# Power.net
KiCad netlist of a schematic drawn in Altium Designer
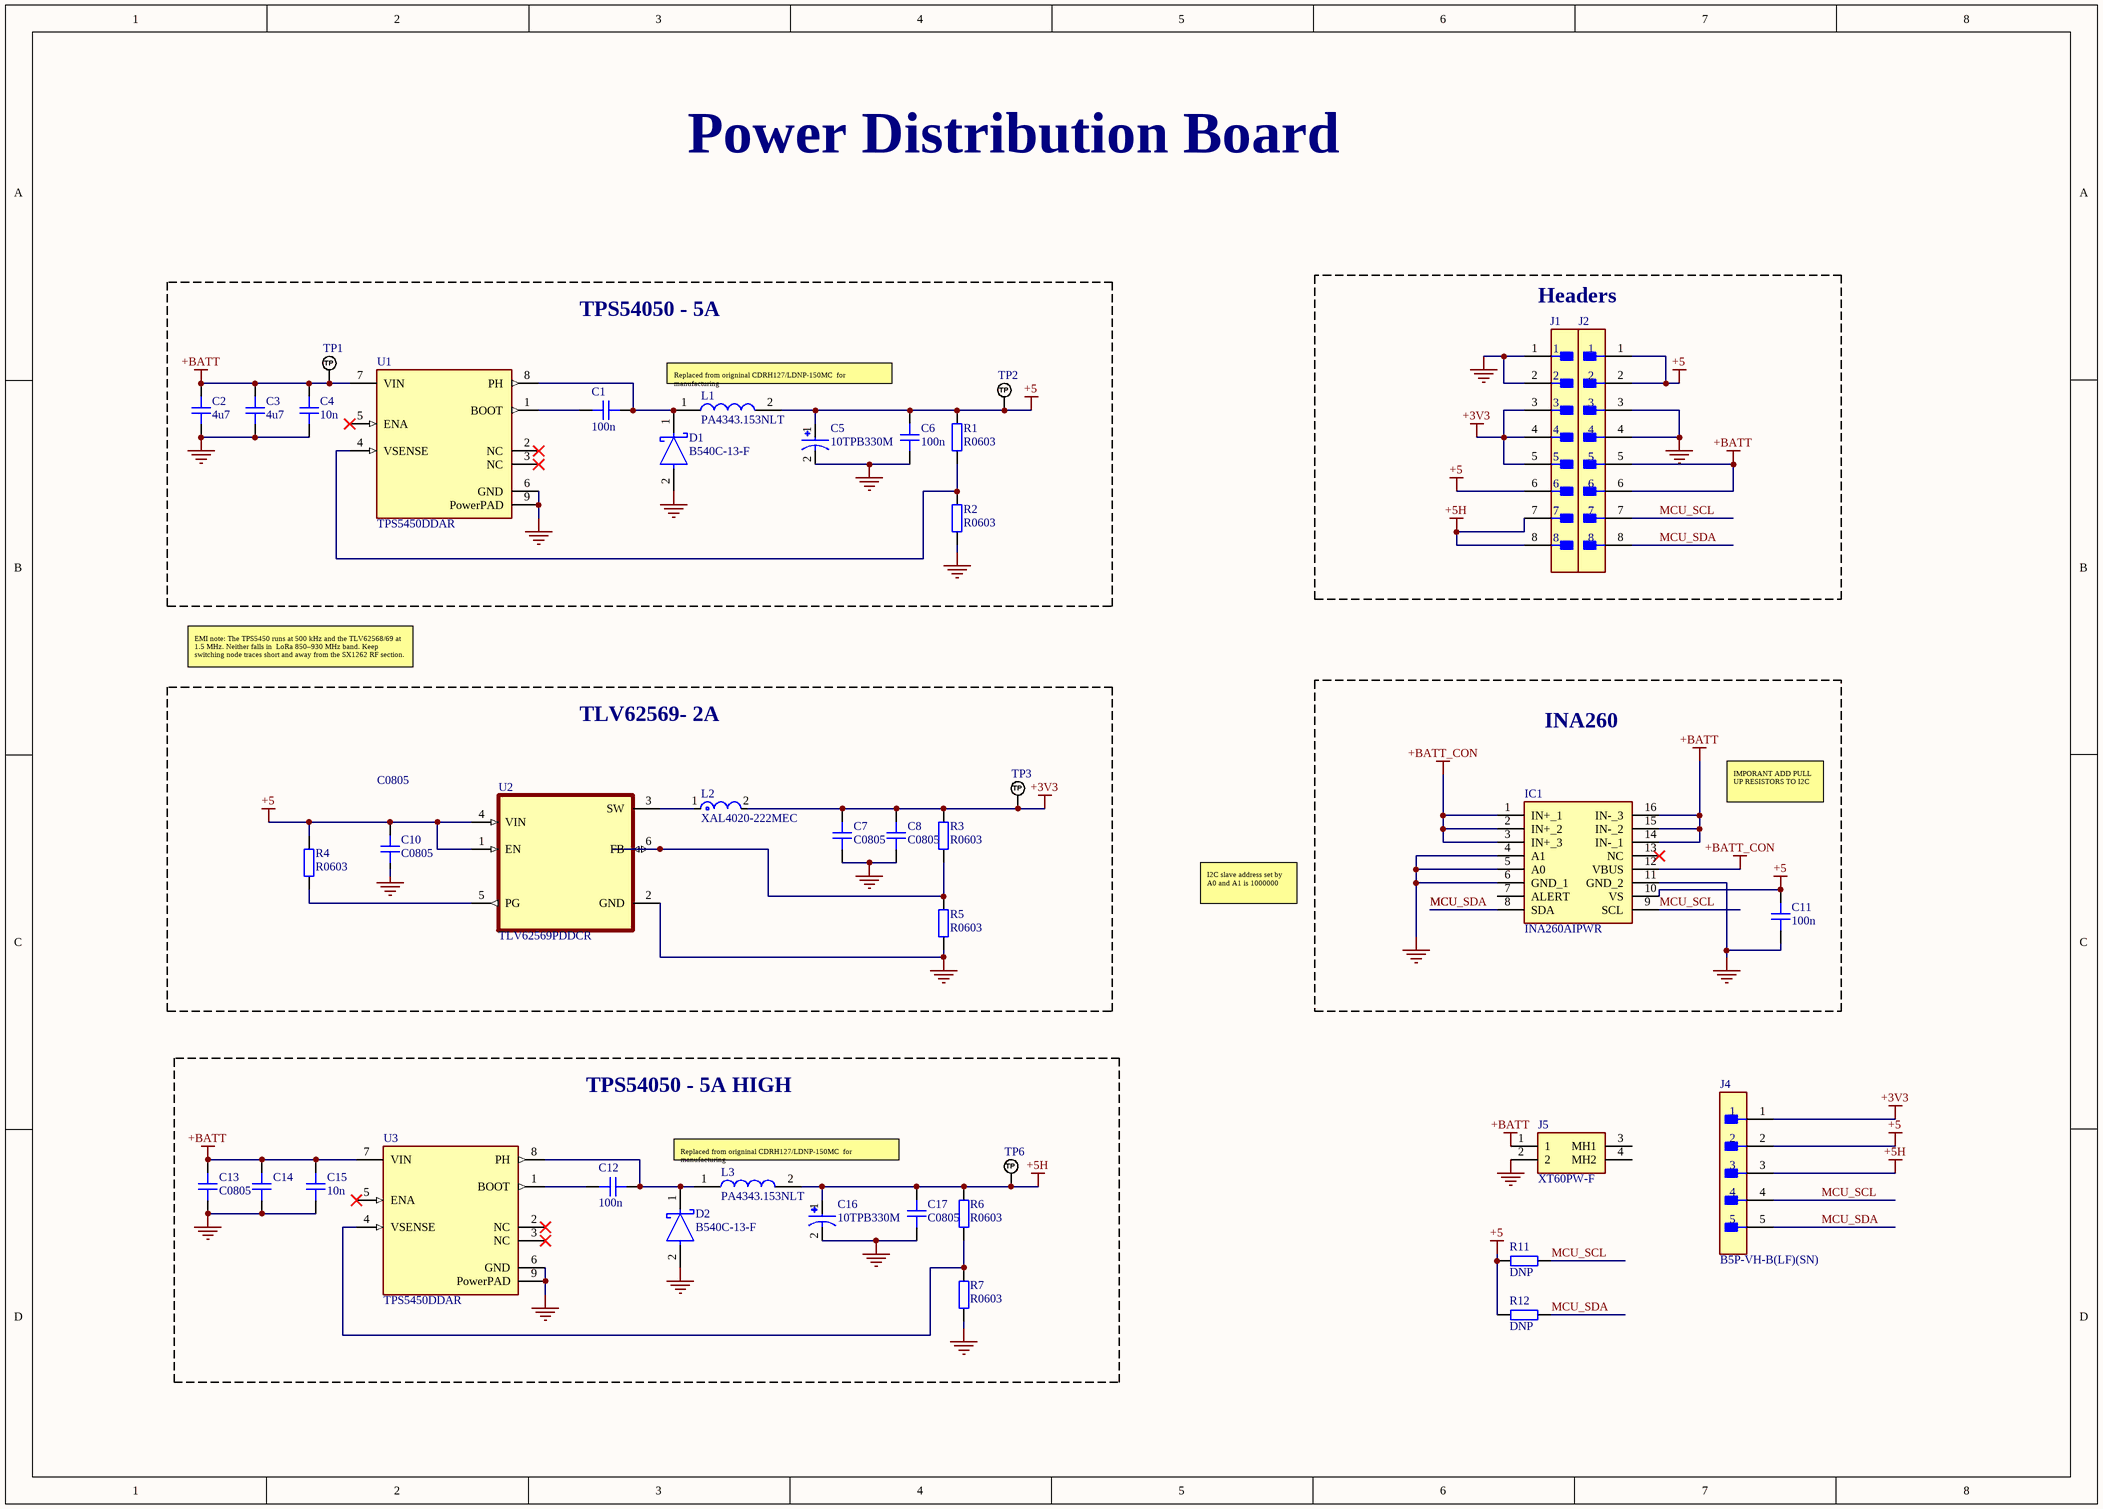
[diagram p0: Power.SchDoc]

(export (version "E")
  (design (tool "Eeschema 10.0.6"))
  (components
    (comp (ref "C1")
      (value "100n")
      (footprint "CAP_0603")
      (description "Capacitor SMD 0603")
      (libsource (lib "Powersch") (part "CAP_0603"))
    )
    (comp (ref "C2")
      (value "4u7")
      (footprint "CAP_0805")
      (description "Capacitor SMD 0805")
      (libsource (lib "Powersch") (part "CAP_0805"))
    )
    (comp (ref "C3")
      (value "4u7")
      (footprint "CAP_0805")
      (description "Capacitor SMD 0805")
      (libsource (lib "Powersch") (part "CAP_0805"))
    )
    (comp (ref "C4")
      (value "10n")
      (footprint "CAP_0603")
      (description "Capacitor SMD 0603")
      (libsource (lib "Powersch") (part "CAP_0603"))
    )
    (comp (ref "C5")
      (value "10TPB330M")
      (footprint "Powerpcblib:CAP_10TPB330M")
      (libsource (lib "Powersch") (part "10TPB330M"))
    )
    (comp (ref "C6")
      (value "100n")
      (footprint "CAP_0805")
      (description "Capacitor SMD 0805")
      (libsource (lib "Powersch") (part "CAP_0805"))
    )
    (comp (ref "C7")
      (value "C0805")
      (footprint "CAP_0805")
      (description "Capacitor SMD 0805")
      (libsource (lib "Powersch") (part "CAP_0805"))
    )
    (comp (ref "C8")
      (value "C0805")
      (footprint "CAP_0805")
      (description "Capacitor SMD 0805")
      (libsource (lib "Powersch") (part "CAP_0805"))
    )
    (comp (ref "C10")
      (value "C0805")
      (footprint "CAP_0805")
      (description "Capacitor SMD 0805")
      (libsource (lib "Powersch") (part "CAP_0805"))
    )
    (comp (ref "C11")
      (value "100n")
      (footprint "CAP_0603")
      (description "Capacitor SMD 0603")
      (libsource (lib "Powersch") (part "CAP_0603"))
    )
    (comp (ref "C12")
      (value "100n")
      (footprint "CAP_0603")
      (description "Capacitor SMD 0603")
      (libsource (lib "Powersch") (part "CAP_0603"))
    )
    (comp (ref "C13")
      (value "C0805")
      (footprint "CAP_0805")
      (description "Capacitor SMD 0805")
      (libsource (lib "Powersch") (part "CAP_0805"))
    )
    (comp (ref "C14")
      (value "C0805")
      (footprint "CAP_0805")
      (description "Capacitor SMD 0805")
      (libsource (lib "Powersch") (part "CAP_0805"))
    )
    (comp (ref "C15")
      (value "10n")
      (footprint "CAP_0603")
      (description "Capacitor SMD 0603")
      (libsource (lib "Powersch") (part "CAP_0603"))
    )
    (comp (ref "C16")
      (value "10TPB330M")
      (footprint "Powerpcblib:CAP_10TPB330M")
      (libsource (lib "Powersch") (part "10TPB330M"))
    )
    (comp (ref "C17")
      (value "C0805")
      (footprint "CAP_0805")
      (description "Capacitor SMD 0805")
      (libsource (lib "Powersch") (part "CAP_0805"))
    )
    (comp (ref "D1")
      (value "B540C-13-F")
      (footprint "FP-SMC-MFG")
      (description "DIODE SCHOTTKY 40V 5A SMC")
      (fields
        (field (name "OCTOPART") "https://octopart.com/b540c-13-f-diodes+inc.-325873")
        (field (name "MANUFACTURER") "Diodes Inc.")
      )
      (libsource (lib "Altium Content Vault") (part "1d6ec82d83fb6aee721767c19dac4b9"))
    )
    (comp (ref "D2")
      (value "B540C-13-F")
      (footprint "FP-SMC-MFG")
      (description "DIODE SCHOTTKY 40V 5A SMC")
      (fields
        (field (name "OCTOPART") "https://octopart.com/b540c-13-f-diodes+inc.-325873")
        (field (name "MANUFACTURER") "Diodes Inc.")
      )
      (libsource (lib "Altium Content Vault") (part "1d6ec82d83fb6aee721767c19dac4b9"))
    )
    (comp (ref "IC1")
      (value "INA260AIPWR")
      (footprint "Powerpcblib:SOP65P640X120-16N")
      (description "Integrated Circuit")
      (fields (field (name "MOUSER PART NUMBER") "595-INA260AIPWR"))
      (libsource (lib "Powersch") (part "INA260AIPWR"))
    )
    (comp (ref "J1")
      (value "TSW-108-08-G-S")
      (footprint "FP-TSW-108-08-G-S-MFG")
      (description "CONN HEADER VERT 8POS 2.54MM")
      (fields
        (field (name "MANUFACTURER") "Samtec")
        (field (name "OCTOPART") "https://octopart.com/tsw-108-08-g-s-samtec-272653")
      )
      (libsource (lib "") (part "99ec2b232beb5d2356d4d77f6a047f0_1"))
    )
    (comp (ref "J2")
      (value "TSW-108-08-G-S")
      (footprint "FP-TSW-108-08-G-S-MFG")
      (description "CONN HEADER VERT 8POS 2.54MM")
      (fields
        (field (name "MANUFACTURER") "Samtec")
        (field (name "OCTOPART") "https://octopart.com/tsw-108-08-g-s-samtec-272653")
      )
      (libsource (lib "Altium Content Vault") (part "99ec2b232beb5d2356d4d77f6a047f0"))
    )
    (comp (ref "J4")
      (value "B5P-VH-B(LF)(SN)")
      (footprint "FP-B5P-VH-B_LF_SN-MFG")
      (description "CONN HEADER VERT 5POS 3.96MM")
      (libsource (lib "Altium Content Vault") (part "bf93c07fd2649a848d0ec8585582aab"))
    )
    (comp (ref "J5")
      (value "XT60PW-F")
      (footprint "SamacSys:XT60PWF")
      (description "Connector")
      (libsource (lib "*") (part "XT60PW-F"))
    )
    (comp (ref "L1")
      (value "PA4343.153NLT")
      (footprint "SamacSys:INDPM140128X650N")
      (description "Inductor")
      (fields (field (name "MOUSER PART NUMBER") "673-PA4343.153NLT"))
      (libsource (lib "Powersch") (part "PA4343.153NLT"))
    )
    (comp (ref "L2")
      (value "XAL4020-222MEC")
      (footprint "FP-XAL4020-MFG")
      (description "Fixed Inductors 2.2uH Shld 20% 5.5A 38.7mOhms AECQ2")
      (fields (field (name "TOLERANCE") "20%"))
      (libsource (lib "Altium Content Vault") (part "4cc4b267dca4c8e51f7102f422741d8"))
    )
    (comp (ref "L3")
      (value "PA4343.153NLT")
      (footprint "SamacSys:INDPM140128X650N")
      (description "Inductor")
      (fields (field (name "MOUSER PART NUMBER") "673-PA4343.153NLT"))
      (libsource (lib "Powersch") (part "PA4343.153NLT"))
    )
    (comp (ref "R1")
      (value "R0603")
      (footprint "RES_0603")
      (description "Resistor SMD 0603")
      (libsource (lib "Powersch") (part "RES_0603"))
    )
    (comp (ref "R2")
      (value "R0603")
      (footprint "RES_0603")
      (description "Resistor SMD 0603")
      (libsource (lib "Powersch") (part "RES_0603"))
    )
    (comp (ref "R3")
      (value "R0603")
      (footprint "RES_0603")
      (description "Resistor SMD 0603")
      (libsource (lib "Powersch") (part "RES_0603"))
    )
    (comp (ref "R4")
      (value "R0603")
      (footprint "RES_0603")
      (description "Resistor SMD 0603")
      (libsource (lib "Powersch") (part "RES_0603"))
    )
    (comp (ref "R5")
      (value "R0603")
      (footprint "RES_0603")
      (description "Resistor SMD 0603")
      (libsource (lib "Powersch") (part "RES_0603"))
    )
    (comp (ref "R6")
      (value "R0603")
      (footprint "RES_0603")
      (description "Resistor SMD 0603")
      (libsource (lib "Powersch") (part "RES_0603"))
    )
    (comp (ref "R7")
      (value "R0603")
      (footprint "RES_0603")
      (description "Resistor SMD 0603")
      (libsource (lib "Powersch") (part "RES_0603"))
    )
    (comp (ref "R11")
      (value "DNP")
      (footprint "RES_0402")
      (description "Resistor SMD 0402")
      (libsource (lib "Powersch") (part "RES_0402"))
    )
    (comp (ref "R12")
      (value "DNP")
      (footprint "RES_0402")
      (description "Resistor SMD 0402")
      (libsource (lib "Powersch") (part "RES_0402"))
    )
    (comp (ref "TP1")
      (value "TEST_POINT_RND_1MM")
      (footprint "PAD_RND_1MM")
      (description "Test Point Round 1mm (NO BOM)")
      (fields (field (name "SOURCE") "Schematic-Lib-PhilsLab.SchLib"))
      (libsource (lib "Shravan Talapady") (part "TEST_POINT_RND_1MM"))
    )
    (comp (ref "TP2")
      (value "TEST_POINT_RND_1MM")
      (footprint "PAD_RND_1MM")
      (description "Test Point Round 1mm (NO BOM)")
      (fields (field (name "SOURCE") "Schematic-Lib-PhilsLab.SchLib"))
      (libsource (lib "Shravan Talapady") (part "TEST_POINT_RND_1MM"))
    )
    (comp (ref "TP3")
      (value "TEST_POINT_RND_1MM")
      (footprint "PAD_RND_1MM")
      (description "Test Point Round 1mm (NO BOM)")
      (fields (field (name "SOURCE") "Schematic-Lib-PhilsLab.SchLib"))
      (libsource (lib "Shravan Talapady") (part "TEST_POINT_RND_1MM"))
    )
    (comp (ref "TP6")
      (value "TEST_POINT_RND_1MM")
      (footprint "PAD_RND_1MM")
      (description "Test Point Round 1mm (NO BOM)")
      (fields (field (name "SOURCE") "Schematic-Lib-PhilsLab.SchLib"))
      (libsource (lib "Shravan Talapady") (part "TEST_POINT_RND_1MM"))
    )
    (comp (ref "U1")
      (value "TPS5450DDAR")
      (footprint "FP-DDA0008J-MFG")
      (description "IC REG BUCK ADJUSTABLE 5A 8SOPWR")
      (fields
        (field (name "MANUFACTURER") "Texas Instruments")
        (field (name "OCTOPART") "https://octopart.com/tps5450ddar-texas+instruments-7105511")
      )
      (libsource (lib "Altium Content Vault") (part "24c0842519a63344fd4f480a1b5e14a"))
    )
    (comp (ref "U2")
      (value "TLV62569PDDCR")
      (footprint "SOT95P280X110-6N")
      (description "2.5V-5.5V input, 2-A high efficiency step-down buck converter in SOT23 and SOT563 package")
      (fields (field (name "MF") "Texas Instruments"))
      (libsource (lib "Powersch") (part "TLV62569PDDCR"))
    )
    (comp (ref "U3")
      (value "TPS5450DDAR")
      (footprint "FP-DDA0008J-MFG")
      (description "IC REG BUCK ADJUSTABLE 5A 8SOPWR")
      (fields
        (field (name "MANUFACTURER") "Texas Instruments")
        (field (name "OCTOPART") "https://octopart.com/tps5450ddar-texas+instruments-7105511")
      )
      (libsource (lib "Altium Content Vault") (part "24c0842519a63344fd4f480a1b5e14a"))
    )
  )
  (nets
    (net (code "1") (name "+3V3") (class "Default")
      (node (ref "C7") (pin "1") (pinfunction "1_1") (pintype "passive"))
      (node (ref "C8") (pin "1") (pinfunction "1_1") (pintype "passive"))
      (node (ref "J1") (pin "3") (pinfunction "3_3") (pintype "passive"))
      (node (ref "J1") (pin "4") (pinfunction "4_4") (pintype "passive"))
      (node (ref "J1") (pin "5") (pinfunction "5_5") (pintype "passive"))
      (node (ref "J4") (pin "1") (pinfunction "1_1") (pintype "passive"))
      (node (ref "L2") (pin "2") (pinfunction "2_2") (pintype "passive"))
      (node (ref "R3") (pin "2") (pinfunction "2_2") (pintype "passive"))
      (node (ref "TP3") (pin "1") (pinfunction "TP_1") (pintype "passive"))
    )
    (net (code "2") (name "+5") (class "Default")
      (node (ref "C10") (pin "1") (pinfunction "1_1") (pintype "passive"))
      (node (ref "C11") (pin "2") (pinfunction "2_2") (pintype "passive"))
      (node (ref "C5") (pin "1") (pinfunction "1_1") (pintype "passive"))
      (node (ref "C6") (pin "1") (pinfunction "1_1") (pintype "passive"))
      (node (ref "IC1") (pin "10") (pinfunction "VS_10") (pintype "passive"))
      (node (ref "J1") (pin "6") (pinfunction "6_6") (pintype "passive"))
      (node (ref "J2") (pin "1") (pinfunction "1_1") (pintype "passive"))
      (node (ref "J2") (pin "2") (pinfunction "2_2") (pintype "passive"))
      (node (ref "J4") (pin "2") (pinfunction "2_2") (pintype "passive"))
      (node (ref "L1") (pin "2") (pinfunction "2_2") (pintype "passive"))
      (node (ref "R1") (pin "2") (pinfunction "2_2") (pintype "passive"))
      (node (ref "R11") (pin "1") (pinfunction "1_1") (pintype "passive"))
      (node (ref "R12") (pin "1") (pinfunction "1_1") (pintype "passive"))
      (node (ref "R4") (pin "2") (pinfunction "2_2") (pintype "passive"))
      (node (ref "TP2") (pin "1") (pinfunction "TP_1") (pintype "passive"))
      (node (ref "U2") (pin "1") (pinfunction "EN_1") (pintype "input"))
      (node (ref "U2") (pin "4") (pinfunction "VIN_4") (pintype "input"))
    )
    (net (code "3") (name "+5H") (class "Default")
      (node (ref "C16") (pin "1") (pinfunction "1_1") (pintype "passive"))
      (node (ref "C17") (pin "1") (pinfunction "1_1") (pintype "passive"))
      (node (ref "J1") (pin "7") (pinfunction "7_7") (pintype "passive"))
      (node (ref "J1") (pin "8") (pinfunction "8_8") (pintype "passive"))
      (node (ref "J4") (pin "3") (pinfunction "3_3") (pintype "passive"))
      (node (ref "L3") (pin "2") (pinfunction "2_2") (pintype "passive"))
      (node (ref "R6") (pin "2") (pinfunction "2_2") (pintype "passive"))
      (node (ref "TP6") (pin "1") (pinfunction "TP_1") (pintype "passive"))
    )
    (net (code "4") (name "+BATT") (class "Default")
      (node (ref "C13") (pin "1") (pinfunction "1_1") (pintype "passive"))
      (node (ref "C14") (pin "1") (pinfunction "1_1") (pintype "passive"))
      (node (ref "C15") (pin "2") (pinfunction "2_2") (pintype "passive"))
      (node (ref "C2") (pin "1") (pinfunction "1_1") (pintype "passive"))
      (node (ref "C3") (pin "1") (pinfunction "1_1") (pintype "passive"))
      (node (ref "C4") (pin "2") (pinfunction "2_2") (pintype "passive"))
      (node (ref "IC1") (pin "14") (pinfunction "IN-_1_14") (pintype "passive"))
      (node (ref "IC1") (pin "15") (pinfunction "IN-_2_15") (pintype "passive"))
      (node (ref "IC1") (pin "16") (pinfunction "IN-_3_16") (pintype "passive"))
      (node (ref "J2") (pin "5") (pinfunction "5_5") (pintype "passive"))
      (node (ref "J2") (pin "6") (pinfunction "6_6") (pintype "passive"))
      (node (ref "J5") (pin "1") (pinfunction "1_1") (pintype "passive"))
      (node (ref "TP1") (pin "1") (pinfunction "TP_1") (pintype "passive"))
      (node (ref "U1") (pin "7") (pinfunction "VIN_7") (pintype "power_in"))
      (node (ref "U3") (pin "7") (pinfunction "VIN_7") (pintype "power_in"))
    )
    (net (code "5") (name "+BATT_CON") (class "Default")
      (node (ref "IC1") (pin "1") (pinfunction "IN+_1_1") (pintype "passive"))
      (node (ref "IC1") (pin "12") (pinfunction "VBUS_12") (pintype "passive"))
      (node (ref "IC1") (pin "2") (pinfunction "IN+_2_2") (pintype "passive"))
      (node (ref "IC1") (pin "3") (pinfunction "IN+_3_3") (pintype "passive"))
    )
    (net (code "6") (name "/MCU_") (class "Default")
      (node (ref "IC1") (pin "8") (pinfunction "SDA_8") (pintype "passive"))
      (node (ref "J2") (pin "8") (pinfunction "8_8") (pintype "passive"))
      (node (ref "J4") (pin "5") (pinfunction "5_5") (pintype "passive"))
      (node (ref "R12") (pin "2") (pinfunction "2_2") (pintype "passive"))
    )
    (net (code "7") (name "/MCU_SCL") (class "Default")
      (node (ref "IC1") (pin "9") (pinfunction "SCL_9") (pintype "passive"))
      (node (ref "J2") (pin "7") (pinfunction "7_7") (pintype "passive"))
      (node (ref "J4") (pin "4") (pinfunction "4_4") (pintype "passive"))
      (node (ref "R11") (pin "2") (pinfunction "2_2") (pintype "passive"))
    )
    (net (code "8") (name "GND") (class "Default")
      (node (ref "C10") (pin "2") (pinfunction "2_2") (pintype "passive"))
      (node (ref "C11") (pin "1") (pinfunction "1_1") (pintype "passive"))
      (node (ref "C13") (pin "2") (pinfunction "2_2") (pintype "passive"))
      (node (ref "C14") (pin "2") (pinfunction "2_2") (pintype "passive"))
      (node (ref "C15") (pin "1") (pinfunction "1_1") (pintype "passive"))
      (node (ref "C16") (pin "2") (pinfunction "2_2") (pintype "passive"))
      (node (ref "C17") (pin "2") (pinfunction "2_2") (pintype "passive"))
      (node (ref "C2") (pin "2") (pinfunction "2_2") (pintype "passive"))
      (node (ref "C3") (pin "2") (pinfunction "2_2") (pintype "passive"))
      (node (ref "C4") (pin "1") (pinfunction "1_1") (pintype "passive"))
      (node (ref "C5") (pin "2") (pinfunction "2_2") (pintype "passive"))
      (node (ref "C6") (pin "2") (pinfunction "2_2") (pintype "passive"))
      (node (ref "C7") (pin "2") (pinfunction "2_2") (pintype "passive"))
      (node (ref "C8") (pin "2") (pinfunction "2_2") (pintype "passive"))
      (node (ref "D1") (pin "2") (pinfunction "A_2") (pintype "passive"))
      (node (ref "D2") (pin "2") (pinfunction "A_2") (pintype "passive"))
      (node (ref "IC1") (pin "11") (pinfunction "GND_2_11") (pintype "passive"))
      (node (ref "IC1") (pin "4") (pinfunction "A1_4") (pintype "passive"))
      (node (ref "IC1") (pin "5") (pinfunction "A0_5") (pintype "passive"))
      (node (ref "IC1") (pin "6") (pinfunction "GND_1_6") (pintype "passive"))
      (node (ref "J1") (pin "1") (pinfunction "1_1") (pintype "passive"))
      (node (ref "J1") (pin "2") (pinfunction "2_2") (pintype "passive"))
      (node (ref "J2") (pin "3") (pinfunction "3_3") (pintype "passive"))
      (node (ref "J2") (pin "4") (pinfunction "4_4") (pintype "passive"))
      (node (ref "J5") (pin "2") (pinfunction "2_2") (pintype "passive"))
      (node (ref "R2") (pin "1") (pinfunction "1_1") (pintype "passive"))
      (node (ref "R5") (pin "1") (pinfunction "1_1") (pintype "passive"))
      (node (ref "R7") (pin "1") (pinfunction "1_1") (pintype "passive"))
      (node (ref "U1") (pin "6") (pinfunction "GND_6") (pintype "power_in"))
      (node (ref "U1") (pin "9") (pinfunction "PowerPAD_9") (pintype "power_in"))
      (node (ref "U2") (pin "2") (pinfunction "GND_2") (pintype "power_in"))
      (node (ref "U3") (pin "6") (pinfunction "GND_6") (pintype "power_in"))
      (node (ref "U3") (pin "9") (pinfunction "PowerPAD_9") (pintype "power_in"))
    )
    (net (code "9") (name "Net-(D1-C)") (class "Default")
      (node (ref "C1") (pin "1") (pinfunction "1_1") (pintype "passive"))
      (node (ref "D1") (pin "1") (pinfunction "C_1") (pintype "passive"))
      (node (ref "L1") (pin "1") (pinfunction "1_1") (pintype "passive"))
      (node (ref "U1") (pin "8") (pinfunction "PH_8") (pintype "output"))
    )
    (net (code "10") (name "Net-(D2-C)") (class "Default")
      (node (ref "C12") (pin "1") (pinfunction "1_1") (pintype "passive"))
      (node (ref "D2") (pin "1") (pinfunction "C_1") (pintype "passive"))
      (node (ref "L3") (pin "1") (pinfunction "1_1") (pintype "passive"))
      (node (ref "U3") (pin "8") (pinfunction "PH_8") (pintype "output"))
    )
    (net (code "11") (name "Net-(U1-BOOT)") (class "Default")
      (node (ref "C1") (pin "2") (pinfunction "2_2") (pintype "passive"))
      (node (ref "U1") (pin "1") (pinfunction "BOOT_1") (pintype "output"))
    )
    (net (code "12") (name "Net-(U1-VSENSE)") (class "Default")
      (node (ref "R1") (pin "1") (pinfunction "1_1") (pintype "passive"))
      (node (ref "R2") (pin "2") (pinfunction "2_2") (pintype "passive"))
      (node (ref "U1") (pin "4") (pinfunction "VSENSE_4") (pintype "input"))
    )
    (net (code "13") (name "Net-(U2-FB)") (class "Default")
      (node (ref "R3") (pin "1") (pinfunction "1_1") (pintype "passive"))
      (node (ref "R5") (pin "2") (pinfunction "2_2") (pintype "passive"))
      (node (ref "U2") (pin "6") (pinfunction "FB_6") (pintype "bidirectional"))
    )
    (net (code "14") (name "Net-(U2-PG)") (class "Default")
      (node (ref "R4") (pin "1") (pinfunction "1_1") (pintype "passive"))
      (node (ref "U2") (pin "5") (pinfunction "PG_5") (pintype "output"))
    )
    (net (code "15") (name "Net-(U2-SW)") (class "Default")
      (node (ref "L2") (pin "1") (pinfunction "1_1") (pintype "passive"))
      (node (ref "U2") (pin "3") (pinfunction "SW_3") (pintype "power_in"))
    )
    (net (code "16") (name "Net-(U3-BOOT)") (class "Default")
      (node (ref "C12") (pin "2") (pinfunction "2_2") (pintype "passive"))
      (node (ref "U3") (pin "1") (pinfunction "BOOT_1") (pintype "output"))
    )
    (net (code "17") (name "Net-(U3-VSENSE)") (class "Default")
      (node (ref "R6") (pin "1") (pinfunction "1_1") (pintype "passive"))
      (node (ref "R7") (pin "2") (pinfunction "2_2") (pintype "passive"))
      (node (ref "U3") (pin "4") (pinfunction "VSENSE_4") (pintype "input"))
    )
    (net (code "18") (name "unconnected-(IC1-ALERT-Pad7)") (class "Default")
      (node (ref "IC1") (pin "7") (pinfunction "ALERT_7") (pintype "passive"))
    )
    (net (code "19") (name "unconnected-(IC1-NC-Pad13)") (class "Default")
      (node (ref "IC1") (pin "13") (pinfunction "NC_13") (pintype "passive+no_connect"))
    )
    (net (code "20") (name "unconnected-(J5-MH1-Pad3)") (class "Default")
      (node (ref "J5") (pin "3") (pinfunction "MH1_3") (pintype "passive"))
    )
    (net (code "21") (name "unconnected-(J5-MH2-Pad4)") (class "Default")
      (node (ref "J5") (pin "4") (pinfunction "MH2_4") (pintype "passive"))
    )
    (net (code "22") (name "unconnected-(U1-ENA-Pad5)") (class "Default")
      (node (ref "U1") (pin "5") (pinfunction "ENA_5") (pintype "input+no_connect"))
    )
    (net (code "23") (name "unconnected-(U1-NC-Pad2)") (class "Default")
      (node (ref "U1") (pin "2") (pinfunction "NC_2") (pintype "passive+no_connect"))
    )
    (net (code "24") (name "unconnected-(U1-NC-Pad3)") (class "Default")
      (node (ref "U1") (pin "3") (pinfunction "NC_3") (pintype "passive+no_connect"))
    )
    (net (code "25") (name "unconnected-(U3-ENA-Pad5)") (class "Default")
      (node (ref "U3") (pin "5") (pinfunction "ENA_5") (pintype "input+no_connect"))
    )
    (net (code "26") (name "unconnected-(U3-NC-Pad2)") (class "Default")
      (node (ref "U3") (pin "2") (pinfunction "NC_2") (pintype "passive+no_connect"))
    )
    (net (code "27") (name "unconnected-(U3-NC-Pad3)") (class "Default")
      (node (ref "U3") (pin "3") (pinfunction "NC_3") (pintype "passive+no_connect"))
    )
  )
)
